# untitled.net
KiCad netlist of a schematic drawn in EAGLE
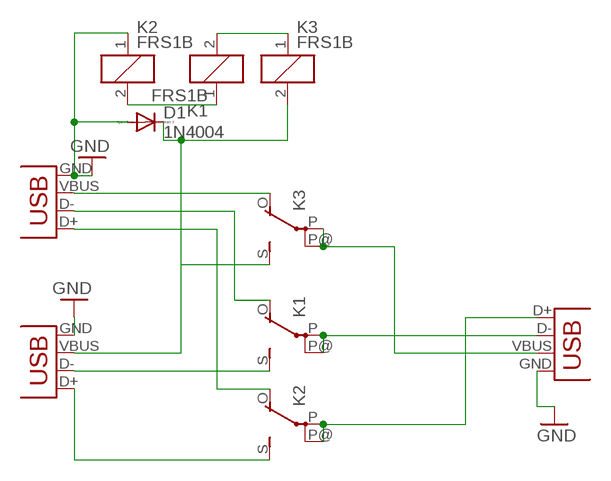
[diagram p0: schematic, sheet 1]

(export (version "E")
  (design (tool "Eeschema 10.0.6"))
  (components
    (comp (ref "D1")
      (value "1N4004")
      (footprint "eagle-import:DO41-10")
      (libsource (lib "eagle-import") (part "1N4004"))
    )
    (comp (ref "K1")
      (value "FRS1B")
      (footprint "eagle-import:FRS1B")
      (libsource (lib "eagle-import") (part "FRS1B"))
    )
    (comp (ref "K2")
      (value "FRS1B")
      (footprint "eagle-import:FRS1B")
      (libsource (lib "eagle-import") (part "FRS1B"))
    )
    (comp (ref "K3")
      (value "FRS1B")
      (footprint "eagle-import:FRS1B")
      (libsource (lib "eagle-import") (part "FRS1B"))
    )
    (comp (ref "X1")
      (value "USB-B-H")
      (footprint "eagle-import:USB-B-H")
      (libsource (lib "eagle-import") (part "USB-B-H"))
    )
    (comp (ref "X2")
      (value "USB-A-H")
      (footprint "eagle-import:USB-A-H")
      (libsource (lib "eagle-import") (part "USB-A-H"))
    )
    (comp (ref "X3")
      (value "USB-A-H")
      (footprint "eagle-import:USB-A-H")
      (libsource (lib "eagle-import") (part "USB-A-H"))
    )
  )
  (nets
    (net (code "1") (name "GND") (class "Default")
      (node (ref "D1") (pin "A") (pinfunction "A_A") (pintype "passive"))
      (node (ref "K2") (pin "1") (pinfunction "1_1") (pintype "passive"))
      (node (ref "X1") (pin "GND") (pinfunction "GND_GND") (pintype "bidirectional"))
      (node (ref "X2") (pin "GND") (pinfunction "GND_GND") (pintype "bidirectional"))
      (node (ref "X3") (pin "GND") (pinfunction "GND_GND") (pintype "bidirectional"))
    )
    (net (code "2") (name "Net-(D1-PadC)") (class "Default")
      (node (ref "D1") (pin "C") (pinfunction "C_C") (pintype "passive"))
      (node (ref "K3") (pin "2") (pinfunction "2_2") (pintype "passive"))
      (node (ref "K3") (pin "S") (pinfunction "S_S") (pintype "passive"))
      (node (ref "X1") (pin "VBUS") (pinfunction "VBUS_VBUS") (pintype "bidirectional"))
    )
    (net (code "3") (name "Net-(K1-Pad1)") (class "Default")
      (node (ref "K1") (pin "1") (pinfunction "1_1") (pintype "passive"))
      (node (ref "K2") (pin "2") (pinfunction "2_2") (pintype "passive"))
    )
    (net (code "4") (name "Net-(K1-Pad2)") (class "Default")
      (node (ref "K1") (pin "2") (pinfunction "2_2") (pintype "passive"))
      (node (ref "K3") (pin "1") (pinfunction "1_1") (pintype "passive"))
    )
    (net (code "5") (name "Net-(K1-PadO)") (class "Default")
      (node (ref "K1") (pin "O") (pinfunction "O_O") (pintype "passive"))
      (node (ref "X2") (pin "D-") (pinfunction "D-_D-") (pintype "bidirectional"))
    )
    (net (code "6") (name "Net-(K1-PadP)") (class "Default")
      (node (ref "K1") (pin "P") (pinfunction "P_P") (pintype "passive"))
      (node (ref "K1") (pin "P@") (pinfunction "P_P@") (pintype "passive"))
      (node (ref "X3") (pin "D-") (pinfunction "D-_D-") (pintype "bidirectional"))
    )
    (net (code "7") (name "Net-(K1-PadS)") (class "Default")
      (node (ref "K1") (pin "S") (pinfunction "S_S") (pintype "passive"))
      (node (ref "X1") (pin "D-") (pinfunction "D-_D-") (pintype "bidirectional"))
    )
    (net (code "8") (name "Net-(K2-PadO)") (class "Default")
      (node (ref "K2") (pin "O") (pinfunction "O_O") (pintype "passive"))
      (node (ref "X2") (pin "D+") (pinfunction "D+_D+") (pintype "bidirectional"))
    )
    (net (code "9") (name "Net-(K2-PadP)") (class "Default")
      (node (ref "K2") (pin "P") (pinfunction "P_P") (pintype "passive"))
      (node (ref "K2") (pin "P@") (pinfunction "P_P@") (pintype "passive"))
      (node (ref "X3") (pin "D+") (pinfunction "D+_D+") (pintype "bidirectional"))
    )
    (net (code "10") (name "Net-(K2-PadS)") (class "Default")
      (node (ref "K2") (pin "S") (pinfunction "S_S") (pintype "passive"))
      (node (ref "X1") (pin "D+") (pinfunction "D+_D+") (pintype "bidirectional"))
    )
    (net (code "11") (name "Net-(K3-PadO)") (class "Default")
      (node (ref "K3") (pin "O") (pinfunction "O_O") (pintype "passive"))
      (node (ref "X2") (pin "VBUS") (pinfunction "VBUS_VBUS") (pintype "bidirectional"))
    )
    (net (code "12") (name "Net-(K3-PadP)") (class "Default")
      (node (ref "K3") (pin "P") (pinfunction "P_P") (pintype "passive"))
      (node (ref "K3") (pin "P@") (pinfunction "P_P@") (pintype "passive"))
      (node (ref "X3") (pin "VBUS") (pinfunction "VBUS_VBUS") (pintype "bidirectional"))
    )
  )
)
